# FanConnector.net
KiCad netlist of a schematic drawn in Altium Designer
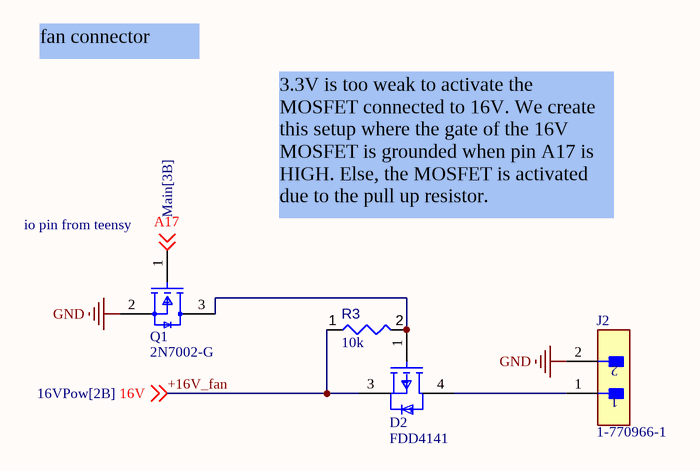
[diagram p0: FanConnector.SchDoc]

(export (version "E")
  (design (tool "Eeschema 10.0.6"))
  (components
    (comp (ref "D2")
      (value "FDD4141")
      (footprint "FP-369AS-MFG")
      (description "MOSFET P-CH 40V 10.8A DPAK")
      (fields
        (field (name "OCTOPART") "https://octopart.com/fdd4141-on+semiconductor-84325802")
        (field (name "MANUFACTURER") "ON Semiconductor")
      )
      (libsource (lib "Altium Content Vault") (part "ec195c925100855187fe8c06440c3e1"))
    )
    (comp (ref "J2")
      (value "1-770966-1")
      (footprint "FP-1-770966-1-MFG")
      (description "CONN HEADER R/A 2POS 4.14MM")
      (fields
        (field (name "OCTOPART") "https://octopart.com/1-770966-1-te+connectivity-46506767")
        (field (name "MANUFACTURER") "TE")
      )
      (libsource (lib "Altium Content Vault") (part "3bc925449376181038e59eaffc5286c"))
    )
    (comp (ref "Q1")
      (value "2N7002-G")
      (footprint "FP-2N7002-G-IPC_C")
      (description "MOSFET N-CH 60V 0.115A SOT23-3")
      (fields
        (field (name "OCTOPART") "https://octopart.com/2n7002-g-microchip-47153309")
        (field (name "MANUFACTURER") "Microchip")
      )
      (libsource (lib "Altium Content Vault") (part "e719174c72bdd709d73c8feae40c216"))
    )
    (comp (ref "R3")
      (value "10k")
      (footprint "RESC0402(1005)_L")
      (description "Chip Resistor, 10 kOhms, +/-1 %, 63 mW, -55 to 125 degC, 0402")
      (fields (field (name "POWER") "63mW") (field (name "TOLERANCE") "1%"))
      (libsource (lib "Alt_ium Course") (part "RES-2"))
    )
  )
  (nets
    (net (code "1") (name "16V") (class "Default")
      (node (ref "D2") (pin "3") (pinfunction "S_3") (pintype "passive"))
      (node (ref "R3") (pin "1") (pinfunction "1_1") (pintype "passive"))
    )
    (net (code "2") (name "A17") (class "Default")
      (node (ref "Q1") (pin "1") (pinfunction "GATE_1") (pintype "passive"))
    )
    (net (code "3") (name "GND") (class "Default")
      (node (ref "J2") (pin "2") (pinfunction "2_2") (pintype "passive"))
      (node (ref "Q1") (pin "2") (pinfunction "SOURCE_2") (pintype "passive"))
    )
    (net (code "4") (name "Net-(D2-D)") (class "Default")
      (node (ref "D2") (pin "4") (pinfunction "D_4") (pintype "passive"))
      (node (ref "J2") (pin "1") (pinfunction "1_1") (pintype "passive"))
    )
    (net (code "5") (name "Net-(D2-G)") (class "Default")
      (node (ref "D2") (pin "1") (pinfunction "G_1") (pintype "passive"))
      (node (ref "Q1") (pin "3") (pinfunction "DRAIN_3") (pintype "passive"))
      (node (ref "R3") (pin "2") (pinfunction "2_2") (pintype "passive"))
    )
  )
)
